# Puente_H.net
KiCad netlist of a schematic drawn in EAGLE
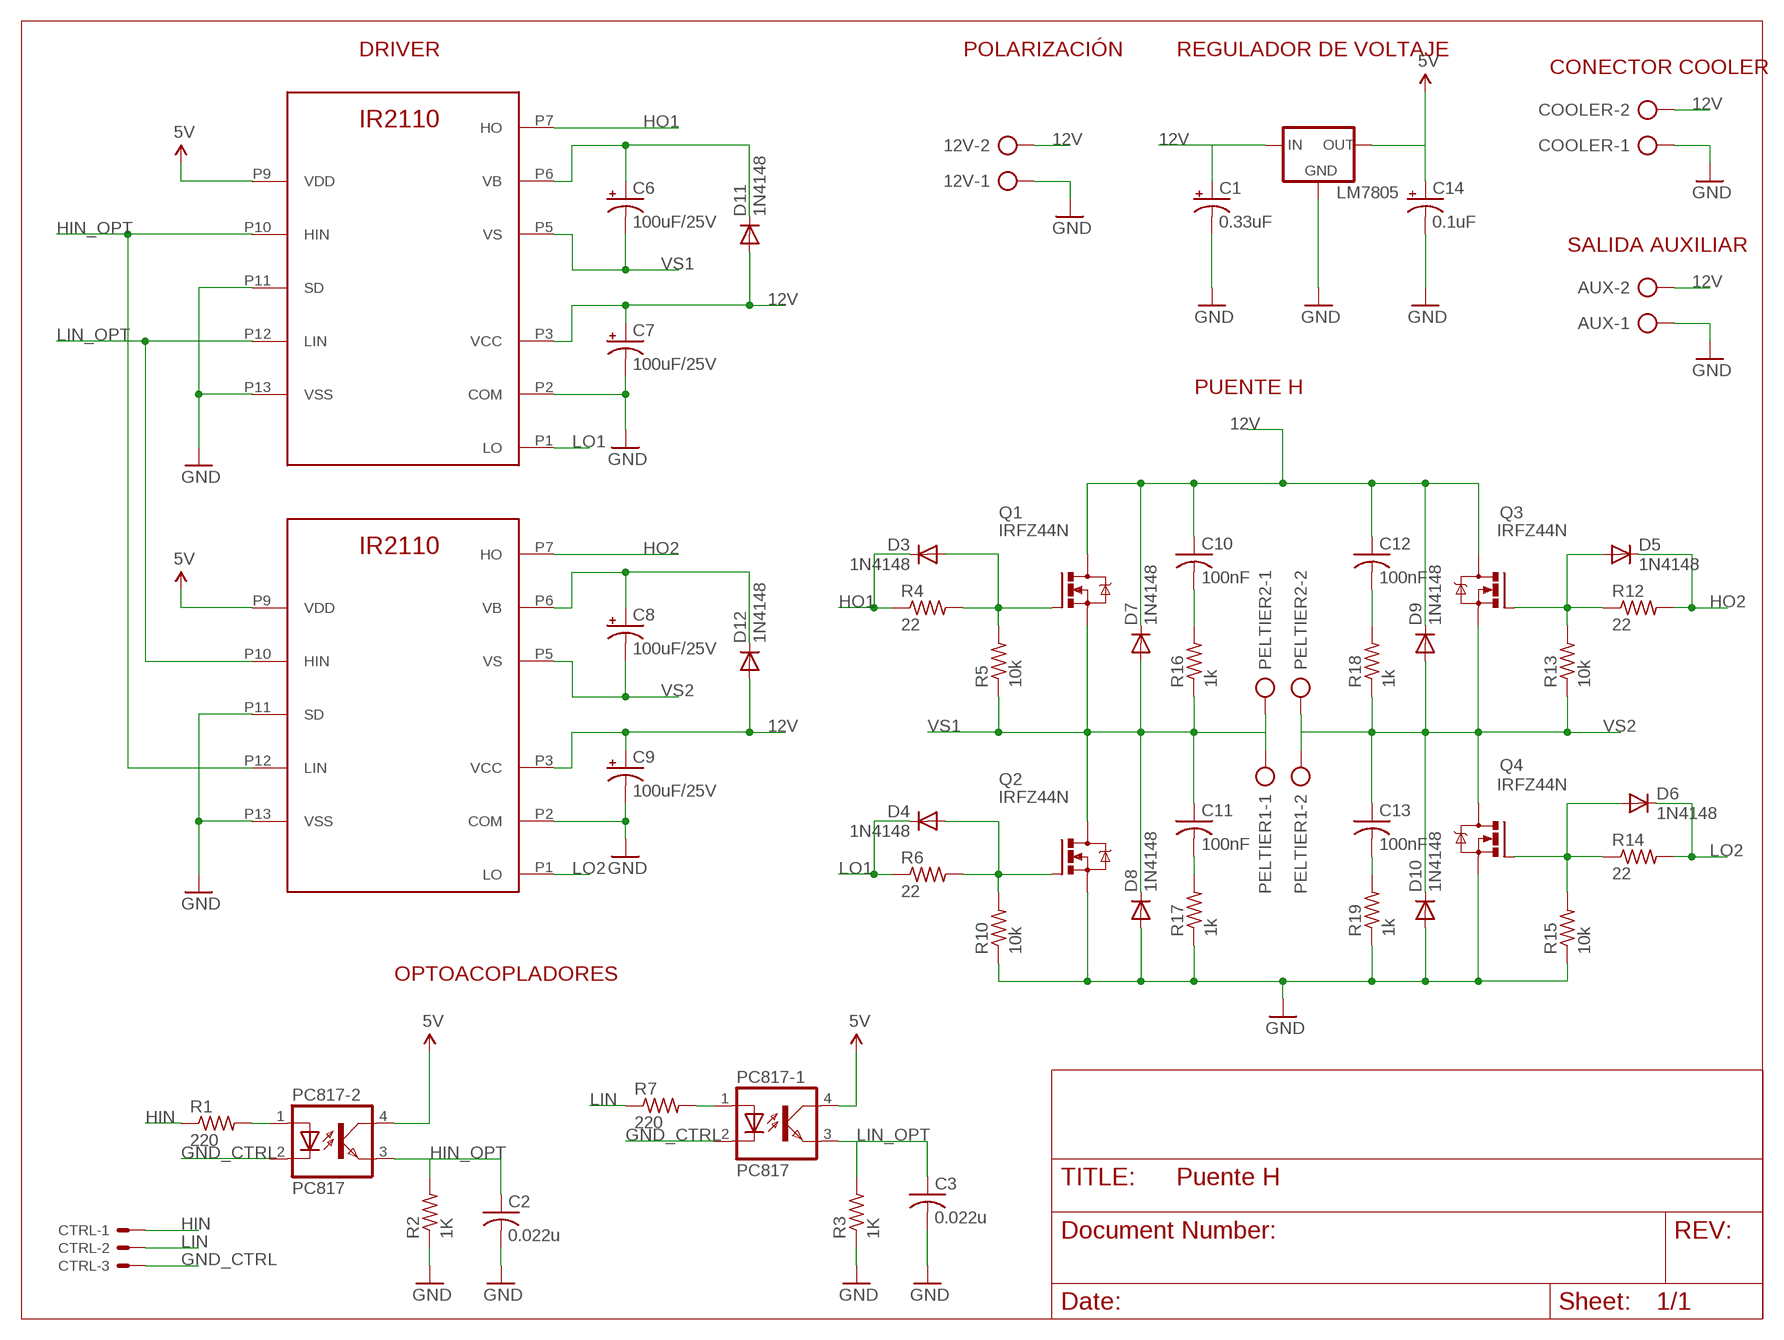
[diagram p0: schematic, sheet 1]

(export (version "E")
  (design (tool "Eeschema 10.0.6"))
  (components
    (comp (ref "12V")
      (value "AK500/2")
      (footprint "eagle-import:AK500_2")
      (libsource (lib "eagle-import") (part "AK500/2"))
    )
    (comp (ref "AUX")
      (value "AK500/2")
      (footprint "eagle-import:AK500_2")
      (libsource (lib "eagle-import") (part "AK500/2"))
    )
    (comp (ref "C1")
      (value "0.33uF")
      (footprint "eagle-import:E2,5-6")
      (libsource (lib "eagle-import") (part "CPOL-USE2.5-6"))
    )
    (comp (ref "C2")
      (value "0.022u")
      (footprint "eagle-import:C102-043X133")
      (libsource (lib "eagle-import") (part "C-US102-043X133"))
    )
    (comp (ref "C3")
      (value "0.022u")
      (footprint "eagle-import:C102-043X133")
      (libsource (lib "eagle-import") (part "C-US102-043X133"))
    )
    (comp (ref "C6")
      (value "100uF/25V")
      (footprint "eagle-import:E2,5-7")
      (libsource (lib "eagle-import") (part "CPOL-USE2.5-7"))
    )
    (comp (ref "C7")
      (value "100uF/25V")
      (footprint "eagle-import:E2,5-7")
      (libsource (lib "eagle-import") (part "CPOL-USE2.5-7"))
    )
    (comp (ref "C8")
      (value "100uF/25V")
      (footprint "eagle-import:E2,5-7")
      (libsource (lib "eagle-import") (part "CPOL-USE2.5-7"))
    )
    (comp (ref "C9")
      (value "100uF/25V")
      (footprint "eagle-import:E2,5-7")
      (libsource (lib "eagle-import") (part "CPOL-USE2.5-7"))
    )
    (comp (ref "C10")
      (value "100nF")
      (footprint "eagle-import:C025-025X050")
      (libsource (lib "eagle-import") (part "C-US025-025X050"))
    )
    (comp (ref "C11")
      (value "100nF")
      (footprint "eagle-import:C025-025X050")
      (libsource (lib "eagle-import") (part "C-US025-025X050"))
    )
    (comp (ref "C12")
      (value "100nF")
      (footprint "eagle-import:C025-025X050")
      (libsource (lib "eagle-import") (part "C-US025-025X050"))
    )
    (comp (ref "C13")
      (value "100nF")
      (footprint "eagle-import:C025-025X050")
      (libsource (lib "eagle-import") (part "C-US025-025X050"))
    )
    (comp (ref "C14")
      (value "0.1uF")
      (footprint "eagle-import:E2,5-6")
      (libsource (lib "eagle-import") (part "CPOL-USE2.5-6"))
    )
    (comp (ref "COOLER")
      (value "AK500/2")
      (footprint "eagle-import:AK500_2")
      (libsource (lib "eagle-import") (part "AK500/2"))
    )
    (comp (ref "CTRL")
      (value "22-23-2031")
      (footprint "eagle-import:22-23-2031")
      (fields (field (name "MF") "MOLEX"))
      (libsource (lib "eagle-import") (part "22-23-2031"))
    )
    (comp (ref "D3")
      (value "1N4148")
      (footprint "eagle-import:DIODE-1N4148")
      (libsource (lib "eagle-import") (part "DIODE1N4148"))
    )
    (comp (ref "D4")
      (value "1N4148")
      (footprint "eagle-import:DIODE-1N4148")
      (libsource (lib "eagle-import") (part "DIODE1N4148"))
    )
    (comp (ref "D5")
      (value "1N4148")
      (footprint "eagle-import:DIODE-1N4148")
      (libsource (lib "eagle-import") (part "DIODE1N4148"))
    )
    (comp (ref "D6")
      (value "1N4148")
      (footprint "eagle-import:DIODE-1N4148")
      (libsource (lib "eagle-import") (part "DIODE1N4148"))
    )
    (comp (ref "D7")
      (value "1N4148")
      (footprint "eagle-import:DIODE-1N4148")
      (libsource (lib "eagle-import") (part "DIODE1N4148"))
    )
    (comp (ref "D8")
      (value "1N4148")
      (footprint "eagle-import:DIODE-1N4148")
      (libsource (lib "eagle-import") (part "DIODE1N4148"))
    )
    (comp (ref "D9")
      (value "1N4148")
      (footprint "eagle-import:DIODE-1N4148")
      (libsource (lib "eagle-import") (part "DIODE1N4148"))
    )
    (comp (ref "D10")
      (value "1N4148")
      (footprint "eagle-import:DIODE-1N4148")
      (libsource (lib "eagle-import") (part "DIODE1N4148"))
    )
    (comp (ref "D11")
      (value "1N4148")
      (footprint "eagle-import:DIODE-1N4148")
      (libsource (lib "eagle-import") (part "DIODE1N4148"))
    )
    (comp (ref "D12")
      (value "1N4148")
      (footprint "eagle-import:DIODE-1N4148")
      (libsource (lib "eagle-import") (part "DIODE1N4148"))
    )
    (comp (ref "IR2110-1")
      (value "IR2110N")
      (footprint "eagle-import:DIL14-1")
      (libsource (lib "eagle-import") (part "IR2110N"))
    )
    (comp (ref "IR2110-2")
      (value "IR2110N")
      (footprint "eagle-import:DIL14-1")
      (libsource (lib "eagle-import") (part "IR2110N"))
    )
    (comp (ref "LM7805")
      (value "78XXS")
      (footprint "eagle-import:78XXS")
      (libsource (lib "eagle-import") (part "78XXS"))
    )
    (comp (ref "PC817-1")
      (value "PC817")
      (footprint "eagle-import:DIL04")
      (fields (field (name "MPN") "PC817X4J000F"))
      (libsource (lib "eagle-import") (part "PC817"))
    )
    (comp (ref "PC817-2")
      (value "PC817")
      (footprint "eagle-import:DIL04")
      (fields (field (name "MPN") "PC817X4J000F"))
      (libsource (lib "eagle-import") (part "PC817"))
    )
    (comp (ref "PELTIER1")
      (value "AK500/2")
      (footprint "eagle-import:AK500_2")
      (libsource (lib "eagle-import") (part "AK500/2"))
    )
    (comp (ref "PELTIER2")
      (value "AK500/2")
      (footprint "eagle-import:AK500_2")
      (libsource (lib "eagle-import") (part "AK500/2"))
    )
    (comp (ref "Q1")
      (value "IRFZ44N")
      (footprint "eagle-import:TO220BV")
      (libsource (lib "eagle-import") (part "IRF520"))
    )
    (comp (ref "Q2")
      (value "IRFZ44N")
      (footprint "eagle-import:TO220BV")
      (libsource (lib "eagle-import") (part "IRF520"))
    )
    (comp (ref "Q3")
      (value "IRFZ44N")
      (footprint "eagle-import:TO220BV")
      (libsource (lib "eagle-import") (part "IRF520"))
    )
    (comp (ref "Q4")
      (value "IRFZ44N")
      (footprint "eagle-import:TO220BV")
      (libsource (lib "eagle-import") (part "IRF520"))
    )
    (comp (ref "R1")
      (value "220")
      (footprint "eagle-import:0207_10")
      (libsource (lib "eagle-import") (part "R-US_0207/10"))
    )
    (comp (ref "R2")
      (value "1K")
      (footprint "eagle-import:0207_10")
      (libsource (lib "eagle-import") (part "R-US_0207/10"))
    )
    (comp (ref "R3")
      (value "1K")
      (footprint "eagle-import:0207_10")
      (libsource (lib "eagle-import") (part "R-US_0207/10"))
    )
    (comp (ref "R4")
      (value "22")
      (footprint "eagle-import:0207_10")
      (libsource (lib "eagle-import") (part "R-US_0207/10"))
    )
    (comp (ref "R5")
      (value "10k")
      (footprint "eagle-import:0207_10")
      (libsource (lib "eagle-import") (part "R-US_0207/10"))
    )
    (comp (ref "R6")
      (value "22")
      (footprint "eagle-import:0207_10")
      (libsource (lib "eagle-import") (part "R-US_0207/10"))
    )
    (comp (ref "R7")
      (value "220")
      (footprint "eagle-import:0207_10")
      (libsource (lib "eagle-import") (part "R-US_0207/10"))
    )
    (comp (ref "R10")
      (value "10k")
      (footprint "eagle-import:0207_10")
      (libsource (lib "eagle-import") (part "R-US_0207/10"))
    )
    (comp (ref "R12")
      (value "22")
      (footprint "eagle-import:0207_10")
      (libsource (lib "eagle-import") (part "R-US_0207/10"))
    )
    (comp (ref "R13")
      (value "10k")
      (footprint "eagle-import:0207_10")
      (libsource (lib "eagle-import") (part "R-US_0207/10"))
    )
    (comp (ref "R14")
      (value "22")
      (footprint "eagle-import:0207_10")
      (libsource (lib "eagle-import") (part "R-US_0207/10"))
    )
    (comp (ref "R15")
      (value "10k")
      (footprint "eagle-import:0207_10")
      (libsource (lib "eagle-import") (part "R-US_0207/10"))
    )
    (comp (ref "R16")
      (value "1k")
      (footprint "eagle-import:0207_10")
      (libsource (lib "eagle-import") (part "R-US_0207/10"))
    )
    (comp (ref "R17")
      (value "1k")
      (footprint "eagle-import:0207_10")
      (libsource (lib "eagle-import") (part "R-US_0207/10"))
    )
    (comp (ref "R18")
      (value "1k")
      (footprint "eagle-import:0207_10")
      (libsource (lib "eagle-import") (part "R-US_0207/10"))
    )
    (comp (ref "R19")
      (value "1k")
      (footprint "eagle-import:0207_10")
      (libsource (lib "eagle-import") (part "R-US_0207/10"))
    )
  )
  (nets
    (net (code "1") (name "/12V") (class "Default")
      (node (ref "12V") (pin "2") (pinfunction "KL_2") (pintype "passive"))
      (node (ref "AUX") (pin "2") (pinfunction "KL_2") (pintype "passive"))
      (node (ref "C1") (pin "+") (pinfunction "+_+") (pintype "passive"))
      (node (ref "C10") (pin "1") (pinfunction "1_1") (pintype "passive"))
      (node (ref "C12") (pin "1") (pinfunction "1_1") (pintype "passive"))
      (node (ref "C7") (pin "+") (pinfunction "+_+") (pintype "passive"))
      (node (ref "C9") (pin "+") (pinfunction "+_+") (pintype "passive"))
      (node (ref "COOLER") (pin "2") (pinfunction "KL_2") (pintype "passive"))
      (node (ref "D11") (pin "A") (pinfunction "A_A") (pintype "passive"))
      (node (ref "D12") (pin "A") (pinfunction "A_A") (pintype "passive"))
      (node (ref "D7") (pin "C") (pinfunction "C_C") (pintype "passive"))
      (node (ref "D9") (pin "C") (pinfunction "C_C") (pintype "passive"))
      (node (ref "IR2110-1") (pin "P3") (pinfunction "VCC_P3") (pintype "bidirectional"))
      (node (ref "IR2110-2") (pin "P3") (pinfunction "VCC_P3") (pintype "bidirectional"))
      (node (ref "LM7805") (pin "IN") (pinfunction "IN_IN") (pintype "input"))
      (node (ref "Q1") (pin "D") (pinfunction "D_D") (pintype "passive"))
      (node (ref "Q3") (pin "D") (pinfunction "D_D") (pintype "passive"))
    )
    (net (code "2") (name "/GND_CTRL") (class "Default")
      (node (ref "CTRL") (pin "3") (pinfunction "S_3") (pintype "passive"))
      (node (ref "PC817-1") (pin "2") (pinfunction "C_2") (pintype "passive"))
      (node (ref "PC817-2") (pin "2") (pinfunction "C_2") (pintype "passive"))
    )
    (net (code "3") (name "/HIN") (class "Default")
      (node (ref "CTRL") (pin "1") (pinfunction "S_1") (pintype "passive"))
      (node (ref "R1") (pin "1") (pinfunction "1_1") (pintype "passive"))
    )
    (net (code "4") (name "/HIN_OPT") (class "Default")
      (node (ref "C2") (pin "1") (pinfunction "1_1") (pintype "passive"))
      (node (ref "IR2110-1") (pin "P10") (pinfunction "HIN_P10") (pintype "bidirectional"))
      (node (ref "IR2110-2") (pin "P12") (pinfunction "LIN_P12") (pintype "bidirectional"))
      (node (ref "PC817-2") (pin "3") (pinfunction "EMIT_3") (pintype "passive"))
      (node (ref "R2") (pin "2") (pinfunction "2_2") (pintype "passive"))
    )
    (net (code "5") (name "/HO1") (class "Default")
      (node (ref "D3") (pin "C") (pinfunction "C_C") (pintype "passive"))
      (node (ref "IR2110-1") (pin "P7") (pinfunction "HO_P7") (pintype "bidirectional"))
      (node (ref "R4") (pin "1") (pinfunction "1_1") (pintype "passive"))
    )
    (net (code "6") (name "/HO2") (class "Default")
      (node (ref "D5") (pin "C") (pinfunction "C_C") (pintype "passive"))
      (node (ref "IR2110-2") (pin "P7") (pinfunction "HO_P7") (pintype "bidirectional"))
      (node (ref "R12") (pin "2") (pinfunction "2_2") (pintype "passive"))
    )
    (net (code "7") (name "/LIN") (class "Default")
      (node (ref "CTRL") (pin "2") (pinfunction "S_2") (pintype "passive"))
      (node (ref "R7") (pin "1") (pinfunction "1_1") (pintype "passive"))
    )
    (net (code "8") (name "/LIN_OPT") (class "Default")
      (node (ref "C3") (pin "1") (pinfunction "1_1") (pintype "passive"))
      (node (ref "IR2110-1") (pin "P12") (pinfunction "LIN_P12") (pintype "bidirectional"))
      (node (ref "IR2110-2") (pin "P10") (pinfunction "HIN_P10") (pintype "bidirectional"))
      (node (ref "PC817-1") (pin "3") (pinfunction "EMIT_3") (pintype "passive"))
      (node (ref "R3") (pin "2") (pinfunction "2_2") (pintype "passive"))
    )
    (net (code "9") (name "/LO1") (class "Default")
      (node (ref "D4") (pin "C") (pinfunction "C_C") (pintype "passive"))
      (node (ref "IR2110-1") (pin "P1") (pinfunction "LO_P1") (pintype "bidirectional"))
      (node (ref "R6") (pin "1") (pinfunction "1_1") (pintype "passive"))
    )
    (net (code "10") (name "/LO2") (class "Default")
      (node (ref "D6") (pin "C") (pinfunction "C_C") (pintype "passive"))
      (node (ref "IR2110-2") (pin "P1") (pinfunction "LO_P1") (pintype "bidirectional"))
      (node (ref "R14") (pin "2") (pinfunction "2_2") (pintype "passive"))
    )
    (net (code "11") (name "/VS1") (class "Default")
      (node (ref "C11") (pin "1") (pinfunction "1_1") (pintype "passive"))
      (node (ref "C6") (pin "-") (pinfunction "-_-") (pintype "passive"))
      (node (ref "D7") (pin "A") (pinfunction "A_A") (pintype "passive"))
      (node (ref "D8") (pin "C") (pinfunction "C_C") (pintype "passive"))
      (node (ref "IR2110-1") (pin "P5") (pinfunction "VS_P5") (pintype "bidirectional"))
      (node (ref "PELTIER1") (pin "1") (pinfunction "KL_1") (pintype "passive"))
      (node (ref "PELTIER2") (pin "1") (pinfunction "KL_1") (pintype "passive"))
      (node (ref "Q1") (pin "S") (pinfunction "S_S") (pintype "passive"))
      (node (ref "Q2") (pin "D") (pinfunction "D_D") (pintype "passive"))
      (node (ref "R16") (pin "1") (pinfunction "1_1") (pintype "passive"))
      (node (ref "R5") (pin "1") (pinfunction "1_1") (pintype "passive"))
    )
    (net (code "12") (name "/VS2") (class "Default")
      (node (ref "C13") (pin "1") (pinfunction "1_1") (pintype "passive"))
      (node (ref "C8") (pin "-") (pinfunction "-_-") (pintype "passive"))
      (node (ref "D10") (pin "C") (pinfunction "C_C") (pintype "passive"))
      (node (ref "D9") (pin "A") (pinfunction "A_A") (pintype "passive"))
      (node (ref "IR2110-2") (pin "P5") (pinfunction "VS_P5") (pintype "bidirectional"))
      (node (ref "PELTIER1") (pin "2") (pinfunction "KL_2") (pintype "passive"))
      (node (ref "PELTIER2") (pin "2") (pinfunction "KL_2") (pintype "passive"))
      (node (ref "Q3") (pin "S") (pinfunction "S_S") (pintype "passive"))
      (node (ref "Q4") (pin "D") (pinfunction "D_D") (pintype "passive"))
      (node (ref "R13") (pin "1") (pinfunction "1_1") (pintype "passive"))
      (node (ref "R18") (pin "1") (pinfunction "1_1") (pintype "passive"))
    )
    (net (code "13") (name "5V") (class "Default")
      (node (ref "C14") (pin "+") (pinfunction "+_+") (pintype "passive"))
      (node (ref "IR2110-1") (pin "P9") (pinfunction "VDD_P9") (pintype "bidirectional"))
      (node (ref "IR2110-2") (pin "P9") (pinfunction "VDD_P9") (pintype "bidirectional"))
      (node (ref "LM7805") (pin "OUT") (pinfunction "OUT_OUT") (pintype "passive"))
      (node (ref "PC817-1") (pin "4") (pinfunction "COL_4") (pintype "passive"))
      (node (ref "PC817-2") (pin "4") (pinfunction "COL_4") (pintype "passive"))
    )
    (net (code "14") (name "GND") (class "Default")
      (node (ref "12V") (pin "1") (pinfunction "KL_1") (pintype "passive"))
      (node (ref "AUX") (pin "1") (pinfunction "KL_1") (pintype "passive"))
      (node (ref "C1") (pin "-") (pinfunction "-_-") (pintype "passive"))
      (node (ref "C14") (pin "-") (pinfunction "-_-") (pintype "passive"))
      (node (ref "C2") (pin "2") (pinfunction "2_2") (pintype "passive"))
      (node (ref "C3") (pin "2") (pinfunction "2_2") (pintype "passive"))
      (node (ref "C7") (pin "-") (pinfunction "-_-") (pintype "passive"))
      (node (ref "C9") (pin "-") (pinfunction "-_-") (pintype "passive"))
      (node (ref "COOLER") (pin "1") (pinfunction "KL_1") (pintype "passive"))
      (node (ref "D10") (pin "A") (pinfunction "A_A") (pintype "passive"))
      (node (ref "D8") (pin "A") (pinfunction "A_A") (pintype "passive"))
      (node (ref "IR2110-1") (pin "P11") (pinfunction "SD_P11") (pintype "bidirectional"))
      (node (ref "IR2110-1") (pin "P13") (pinfunction "VSS_P13") (pintype "bidirectional"))
      (node (ref "IR2110-1") (pin "P2") (pinfunction "COM_P2") (pintype "bidirectional"))
      (node (ref "IR2110-2") (pin "P11") (pinfunction "SD_P11") (pintype "bidirectional"))
      (node (ref "IR2110-2") (pin "P13") (pinfunction "VSS_P13") (pintype "bidirectional"))
      (node (ref "IR2110-2") (pin "P2") (pinfunction "COM_P2") (pintype "bidirectional"))
      (node (ref "LM7805") (pin "GND") (pinfunction "GND_GND") (pintype "input"))
      (node (ref "Q2") (pin "S") (pinfunction "S_S") (pintype "passive"))
      (node (ref "Q4") (pin "S") (pinfunction "S_S") (pintype "passive"))
      (node (ref "R10") (pin "1") (pinfunction "1_1") (pintype "passive"))
      (node (ref "R15") (pin "1") (pinfunction "1_1") (pintype "passive"))
      (node (ref "R17") (pin "1") (pinfunction "1_1") (pintype "passive"))
      (node (ref "R19") (pin "1") (pinfunction "1_1") (pintype "passive"))
      (node (ref "R2") (pin "1") (pinfunction "1_1") (pintype "passive"))
      (node (ref "R3") (pin "1") (pinfunction "1_1") (pintype "passive"))
    )
    (net (code "15") (name "Net-(C10-Pad2)") (class "Default")
      (node (ref "C10") (pin "2") (pinfunction "2_2") (pintype "passive"))
      (node (ref "R16") (pin "2") (pinfunction "2_2") (pintype "passive"))
    )
    (net (code "16") (name "Net-(C11-Pad2)") (class "Default")
      (node (ref "C11") (pin "2") (pinfunction "2_2") (pintype "passive"))
      (node (ref "R17") (pin "2") (pinfunction "2_2") (pintype "passive"))
    )
    (net (code "17") (name "Net-(C12-Pad2)") (class "Default")
      (node (ref "C12") (pin "2") (pinfunction "2_2") (pintype "passive"))
      (node (ref "R18") (pin "2") (pinfunction "2_2") (pintype "passive"))
    )
    (net (code "18") (name "Net-(C13-Pad2)") (class "Default")
      (node (ref "C13") (pin "2") (pinfunction "2_2") (pintype "passive"))
      (node (ref "R19") (pin "2") (pinfunction "2_2") (pintype "passive"))
    )
    (net (code "19") (name "Net-(D3-PadA)") (class "Default")
      (node (ref "D3") (pin "A") (pinfunction "A_A") (pintype "passive"))
      (node (ref "Q1") (pin "G") (pinfunction "G_G") (pintype "passive"))
      (node (ref "R4") (pin "2") (pinfunction "2_2") (pintype "passive"))
      (node (ref "R5") (pin "2") (pinfunction "2_2") (pintype "passive"))
    )
    (net (code "20") (name "Net-(D4-PadA)") (class "Default")
      (node (ref "D4") (pin "A") (pinfunction "A_A") (pintype "passive"))
      (node (ref "Q2") (pin "G") (pinfunction "G_G") (pintype "passive"))
      (node (ref "R10") (pin "2") (pinfunction "2_2") (pintype "passive"))
      (node (ref "R6") (pin "2") (pinfunction "2_2") (pintype "passive"))
    )
    (net (code "21") (name "Net-(D5-PadA)") (class "Default")
      (node (ref "D5") (pin "A") (pinfunction "A_A") (pintype "passive"))
      (node (ref "Q3") (pin "G") (pinfunction "G_G") (pintype "passive"))
      (node (ref "R12") (pin "1") (pinfunction "1_1") (pintype "passive"))
      (node (ref "R13") (pin "2") (pinfunction "2_2") (pintype "passive"))
    )
    (net (code "22") (name "Net-(D6-PadA)") (class "Default")
      (node (ref "D6") (pin "A") (pinfunction "A_A") (pintype "passive"))
      (node (ref "Q4") (pin "G") (pinfunction "G_G") (pintype "passive"))
      (node (ref "R14") (pin "1") (pinfunction "1_1") (pintype "passive"))
      (node (ref "R15") (pin "2") (pinfunction "2_2") (pintype "passive"))
    )
    (net (code "23") (name "Net-(IR2110-1-VB)") (class "Default")
      (node (ref "C6") (pin "+") (pinfunction "+_+") (pintype "passive"))
      (node (ref "D11") (pin "C") (pinfunction "C_C") (pintype "passive"))
      (node (ref "IR2110-1") (pin "P6") (pinfunction "VB_P6") (pintype "bidirectional"))
    )
    (net (code "24") (name "Net-(IR2110-2-VB)") (class "Default")
      (node (ref "C8") (pin "+") (pinfunction "+_+") (pintype "passive"))
      (node (ref "D12") (pin "C") (pinfunction "C_C") (pintype "passive"))
      (node (ref "IR2110-2") (pin "P6") (pinfunction "VB_P6") (pintype "bidirectional"))
    )
    (net (code "25") (name "Net-(PC817-1-A)") (class "Default")
      (node (ref "PC817-1") (pin "1") (pinfunction "A_1") (pintype "passive"))
      (node (ref "R7") (pin "2") (pinfunction "2_2") (pintype "passive"))
    )
    (net (code "26") (name "Net-(PC817-2-A)") (class "Default")
      (node (ref "PC817-2") (pin "1") (pinfunction "A_1") (pintype "passive"))
      (node (ref "R1") (pin "2") (pinfunction "2_2") (pintype "passive"))
    )
  )
)
